# CHECK_BATTERY.net
KiCad netlist of a schematic drawn in Altium Designer
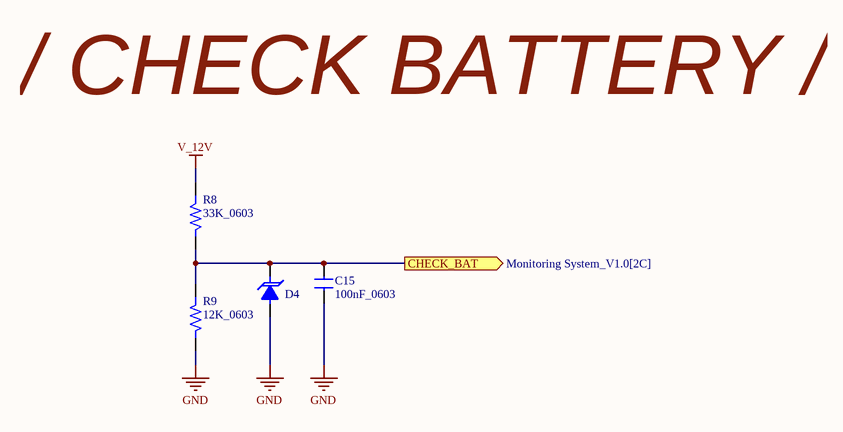
[diagram p0: CHECK_BATTERY.SchDoc]

(export (version "E")
  (design (tool "Eeschema 10.0.6"))
  (components
    (comp (ref "C15")
      (value "100nF_0603")
      (footprint "CN-SMD-0603")
      (description "Cap SMD, 0.06x0.03 inch, 1.55x0.85 mm - 1608")
      (libsource (lib "LYAM_LIB") (part "CAP 0603 104"))
    )
    (comp (ref "D4")
      (value "SMBJ5.0A_KE")
      (footprint "SMB")
      (description "TVS Diode, Vrrm =5.0V, Vcl = 9.2V")
      (fields (field (name "PUBLISHER") "Altium Limited"))
      (libsource (lib "LYAM_LIB") (part "Diode SMBJ5.0A"))
    )
    (comp (ref "R8")
      (value "33K_0603")
      (footprint "RES-SMD-0603")
      (description "Resistor SMD, 0.06x0.03 inch, 1.55x0.85 mm - 1608, 1/10W")
      (libsource (lib "LYAM_LIB") (part "RES 0603 33K"))
    )
    (comp (ref "R9")
      (value "12K_0603")
      (footprint "RES-SMD-0603")
      (description "Resistor SMD, 0.06x0.03 inch, 1.55x0.85 mm - 1608, 1/10W")
      (libsource (lib "LYAM_LIB") (part "RES 0603 12K"))
    )
  )
  (nets
    (net (code "1") (name "/CHECK_BAT") (class "Default")
      (node (ref "C15") (pin "2") (pinfunction "2_2") (pintype "passive"))
      (node (ref "D4") (pin "2") (pinfunction "K_2") (pintype "passive"))
      (node (ref "R8") (pin "1") (pinfunction "1_1") (pintype "passive"))
      (node (ref "R9") (pin "2") (pinfunction "2_2") (pintype "passive"))
    )
    (net (code "2") (name "GND") (class "Default")
      (node (ref "C15") (pin "1") (pinfunction "1_1") (pintype "passive"))
      (node (ref "D4") (pin "1") (pinfunction "A_1") (pintype "passive"))
      (node (ref "R9") (pin "1") (pinfunction "1_1") (pintype "passive"))
    )
    (net (code "3") (name "V_12V") (class "Default")
      (node (ref "R8") (pin "2") (pinfunction "2_2") (pintype "passive"))
    )
  )
)
